# Input_Current_Limiting.net
KiCad netlist of a schematic drawn in Altium Designer
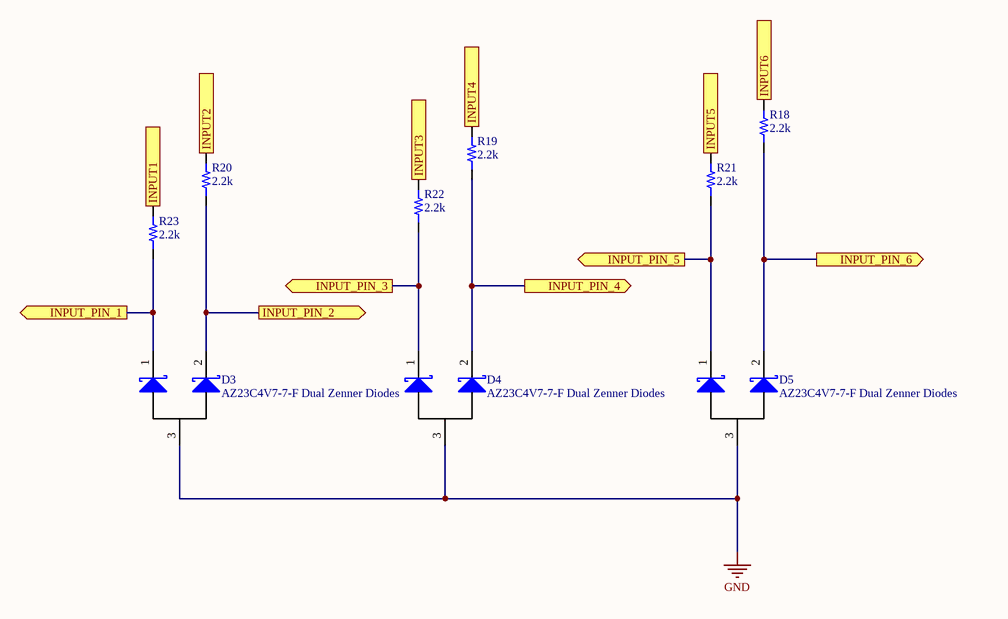
[diagram p0: Input_Current_Limiting.SchDoc]

(export (version "E")
  (design (tool "Eeschema 10.0.6"))
  (components
    (comp (ref "D3")
      (value "AZ23C4V7-7-F Dual Zenner Diodes")
      (footprint "SOT23-3")
      (description "DIODE ZENER ARRAY 4.7V SOT23-3")
      (fields
        (field (name "POWER") "300mW")
        (field (name "MFRPARTNO") "AZ23C4V7-7-F")
        (field (name "CREATED_BY") "Angel Delgado")
      )
      (libsource (lib "Altium-Lib") (part "AZ23C4V7-7-F Dual Zenner Diodes"))
    )
    (comp (ref "D4")
      (value "AZ23C4V7-7-F Dual Zenner Diodes")
      (footprint "SOT23-3")
      (description "DIODE ZENER ARRAY 4.7V SOT23-3")
      (fields
        (field (name "POWER") "300mW")
        (field (name "MFRPARTNO") "AZ23C4V7-7-F")
        (field (name "CREATED_BY") "Angel Delgado")
      )
      (libsource (lib "Altium-Lib") (part "AZ23C4V7-7-F Dual Zenner Diodes"))
    )
    (comp (ref "D5")
      (value "AZ23C4V7-7-F Dual Zenner Diodes")
      (footprint "SOT23-3")
      (description "DIODE ZENER ARRAY 4.7V SOT23-3")
      (fields
        (field (name "POWER") "300mW")
        (field (name "MFRPARTNO") "AZ23C4V7-7-F")
        (field (name "CREATED_BY") "Angel Delgado")
      )
      (libsource (lib "Altium-Lib") (part "AZ23C4V7-7-F Dual Zenner Diodes"))
    )
    (comp (ref "R18")
      (value "2.2k")
      (footprint "RES 0603/1608")
      (fields
        (field (name "TOLERANCE") "1%")
        (field (name "POWER") "1/10W")
        (field (name "Comment") "Resistor 2.2k 0603 1/10W 1%")
        (field (name "CREATED_BY") "Nick Mah")
      )
      (libsource (lib "Altium-Lib") (part "Resistor"))
    )
    (comp (ref "R19")
      (value "2.2k")
      (footprint "RES 0603/1608")
      (fields
        (field (name "TOLERANCE") "1%")
        (field (name "POWER") "1/10W")
        (field (name "Comment") "Resistor 2.2k 0603 1/10W 1%")
        (field (name "CREATED_BY") "Nick Mah")
      )
      (libsource (lib "Altium-Lib") (part "Resistor"))
    )
    (comp (ref "R20")
      (value "2.2k")
      (footprint "RES 0603/1608")
      (fields
        (field (name "TOLERANCE") "1%")
        (field (name "POWER") "1/10W")
        (field (name "Comment") "Resistor 2.2k 0603 1/10W 1%")
        (field (name "CREATED_BY") "Nick Mah")
      )
      (libsource (lib "Altium-Lib") (part "Resistor"))
    )
    (comp (ref "R21")
      (value "2.2k")
      (footprint "RES 0603/1608")
      (fields
        (field (name "TOLERANCE") "1%")
        (field (name "POWER") "1/10W")
        (field (name "Comment") "Resistor 2.2k 0603 1/10W 1%")
        (field (name "CREATED_BY") "Nick Mah")
      )
      (libsource (lib "Altium-Lib") (part "Resistor"))
    )
    (comp (ref "R22")
      (value "2.2k")
      (footprint "RES 0603/1608")
      (fields
        (field (name "TOLERANCE") "1%")
        (field (name "POWER") "1/10W")
        (field (name "Comment") "Resistor 2.2k 0603 1/10W 1%")
        (field (name "CREATED_BY") "Nick Mah")
      )
      (libsource (lib "Altium-Lib") (part "Resistor"))
    )
    (comp (ref "R23")
      (value "2.2k")
      (footprint "RES 0603/1608")
      (fields
        (field (name "TOLERANCE") "1%")
        (field (name "POWER") "1/10W")
        (field (name "Comment") "Resistor 2.2k 0603 1/10W 1%")
        (field (name "CREATED_BY") "Nick Mah")
      )
      (libsource (lib "Altium-Lib") (part "Resistor"))
    )
  )
  (nets
    (net (code "1") (name "/INPUT1") (class "Default")
      (node (ref "R23") (pin "2") (pinfunction "2_2") (pintype "passive"))
    )
    (net (code "2") (name "/INPUT2") (class "Default")
      (node (ref "R20") (pin "2") (pinfunction "2_2") (pintype "passive"))
    )
    (net (code "3") (name "/INPUT3") (class "Default")
      (node (ref "R22") (pin "2") (pinfunction "2_2") (pintype "passive"))
    )
    (net (code "4") (name "/INPUT4") (class "Default")
      (node (ref "R19") (pin "2") (pinfunction "2_2") (pintype "passive"))
    )
    (net (code "5") (name "/INPUT5") (class "Default")
      (node (ref "R21") (pin "2") (pinfunction "2_2") (pintype "passive"))
    )
    (net (code "6") (name "/INPUT6") (class "Default")
      (node (ref "R18") (pin "2") (pinfunction "2_2") (pintype "passive"))
    )
    (net (code "7") (name "/INPUT_PIN_1") (class "Default")
      (node (ref "D3") (pin "1") (pinfunction "1_1") (pintype "passive"))
      (node (ref "R23") (pin "1") (pinfunction "1_1") (pintype "passive"))
    )
    (net (code "8") (name "/INPUT_PIN_2") (class "Default")
      (node (ref "D3") (pin "2") (pinfunction "2_2") (pintype "passive"))
      (node (ref "R20") (pin "1") (pinfunction "1_1") (pintype "passive"))
    )
    (net (code "9") (name "/INPUT_PIN_3") (class "Default")
      (node (ref "D4") (pin "1") (pinfunction "1_1") (pintype "passive"))
      (node (ref "R22") (pin "1") (pinfunction "1_1") (pintype "passive"))
    )
    (net (code "10") (name "/INPUT_PIN_4") (class "Default")
      (node (ref "D4") (pin "2") (pinfunction "2_2") (pintype "passive"))
      (node (ref "R19") (pin "1") (pinfunction "1_1") (pintype "passive"))
    )
    (net (code "11") (name "/INPUT_PIN_5") (class "Default")
      (node (ref "D5") (pin "1") (pinfunction "1_1") (pintype "passive"))
      (node (ref "R21") (pin "1") (pinfunction "1_1") (pintype "passive"))
    )
    (net (code "12") (name "/INPUT_PIN_6") (class "Default")
      (node (ref "D5") (pin "2") (pinfunction "2_2") (pintype "passive"))
      (node (ref "R18") (pin "1") (pinfunction "1_1") (pintype "passive"))
    )
    (net (code "13") (name "GND") (class "Default")
      (node (ref "D3") (pin "3") (pinfunction "3_3") (pintype "passive"))
      (node (ref "D4") (pin "3") (pinfunction "3_3") (pintype "passive"))
      (node (ref "D5") (pin "3") (pinfunction "3_3") (pintype "passive"))
    )
  )
)
